# emonGLCD_V1_4.net
KiCad netlist of a schematic drawn in EAGLE
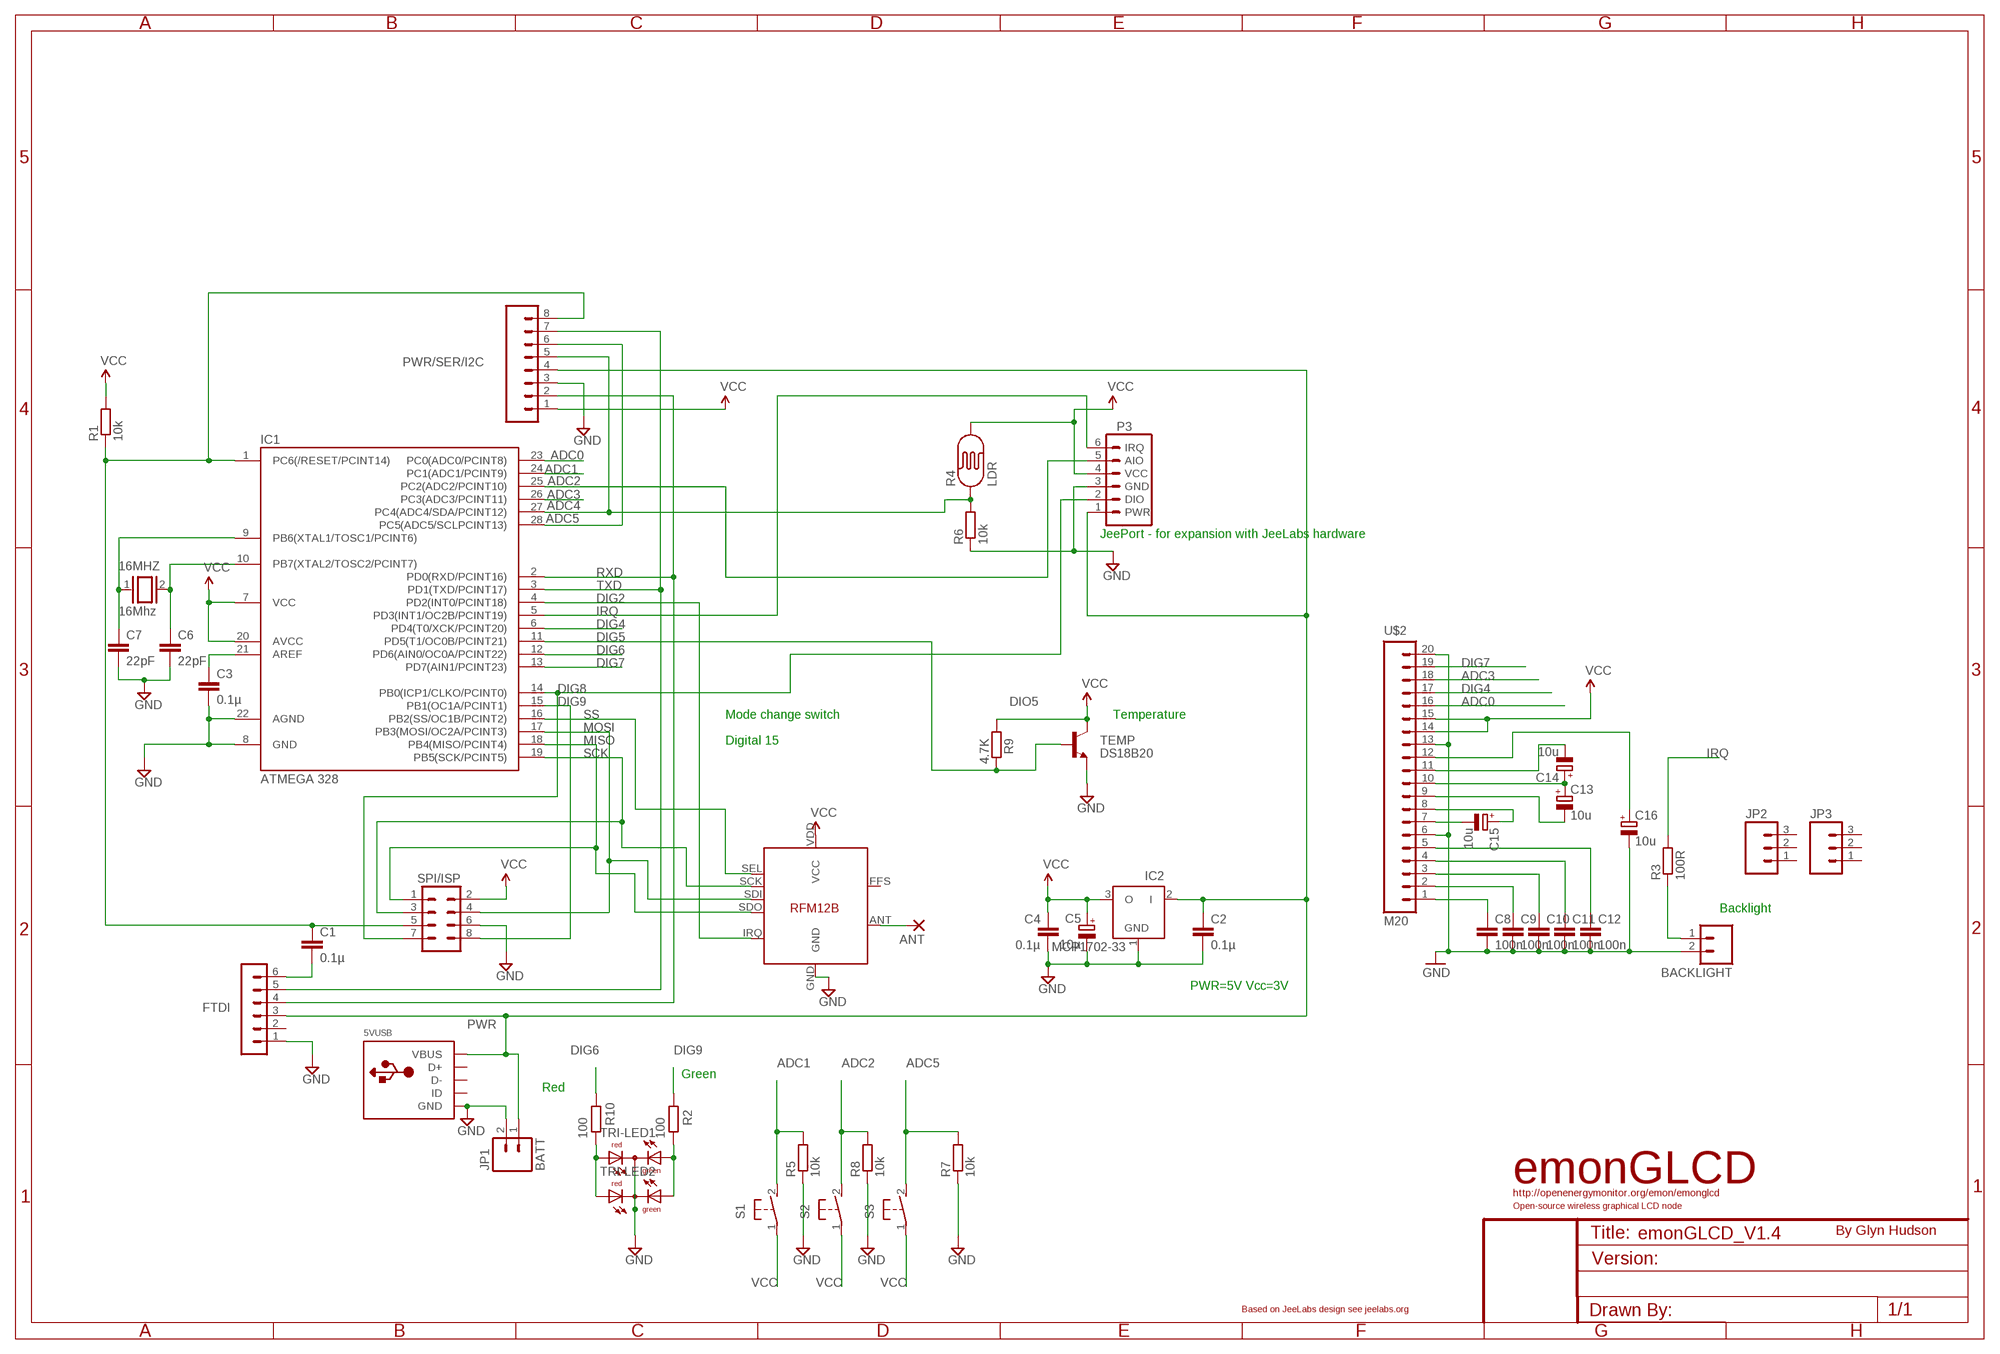
[diagram p0: schematic, sheet 1]

(export (version "E")
  (design (tool "Eeschema 10.0.6"))
  (components
    (comp (ref "5VUSB")
      (value "USBMOLEX")
      (footprint "eagle-import:USB-MINIB-THM-MOLEX")
      (libsource (lib "eagle-import") (part "USBMOLEX"))
    )
    (comp (ref "16MHZ")
      (value "16Mhz")
      (footprint "eagle-import:QS")
      (libsource (lib "eagle-import") (part "XTAL/S"))
    )
    (comp (ref "ANT")
      (value "1,6/0,8")
      (footprint "eagle-import:1,6_0,8")
      (libsource (lib "eagle-import") (part "1,6/0,8"))
    )
    (comp (ref "BACKLIGHT")
      (value "M02PTH")
      (footprint "eagle-import:1X02")
      (libsource (lib "eagle-import") (part "M02PTH"))
    )
    (comp (ref "C1")
      (value "0.1µ")
      (footprint "eagle-import:C025-024X044")
      (libsource (lib "eagle-import") (part "C-EU025-024X044"))
    )
    (comp (ref "C2")
      (value "0.1µ")
      (footprint "eagle-import:C025-024X044")
      (libsource (lib "eagle-import") (part "C-EU025-024X044"))
    )
    (comp (ref "C3")
      (value "0.1µ")
      (footprint "eagle-import:C025-024X044")
      (libsource (lib "eagle-import") (part "C-EU025-024X044"))
    )
    (comp (ref "C4")
      (value "0.1µ")
      (footprint "eagle-import:C025-024X044")
      (libsource (lib "eagle-import") (part "C-EU025-024X044"))
    )
    (comp (ref "C5")
      (value "10µ")
      (footprint "eagle-import:E1,8-4")
      (libsource (lib "eagle-import") (part "CPOL-EUE1.8-4"))
    )
    (comp (ref "C6")
      (value "22pF")
      (footprint "eagle-import:C2.5-2")
      (libsource (lib "eagle-import") (part "C2.5/2"))
    )
    (comp (ref "C7")
      (value "22pF")
      (footprint "eagle-import:C2.5-2")
      (libsource (lib "eagle-import") (part "C2.5/2"))
    )
    (comp (ref "C8")
      (value "100n")
      (footprint "eagle-import:C2.5-2")
      (libsource (lib "eagle-import") (part "C2.5/2"))
    )
    (comp (ref "C9")
      (value "100n")
      (footprint "eagle-import:C2.5-2")
      (libsource (lib "eagle-import") (part "C2.5/2"))
    )
    (comp (ref "C10")
      (value "100n")
      (footprint "eagle-import:C2.5-2")
      (libsource (lib "eagle-import") (part "C2.5/2"))
    )
    (comp (ref "C11")
      (value "100n")
      (footprint "eagle-import:C2.5-2")
      (libsource (lib "eagle-import") (part "C2.5/2"))
    )
    (comp (ref "C12")
      (value "100n")
      (footprint "eagle-import:C2.5-2")
      (libsource (lib "eagle-import") (part "C2.5/2"))
    )
    (comp (ref "C13")
      (value "10u")
      (footprint "eagle-import:E1,8-4")
      (libsource (lib "eagle-import") (part "CPOL-EUE1.8-4"))
    )
    (comp (ref "C14")
      (value "10u")
      (footprint "eagle-import:E1,8-4")
      (libsource (lib "eagle-import") (part "CPOL-EUE1.8-4"))
    )
    (comp (ref "C15")
      (value "10u")
      (footprint "eagle-import:E1,8-4")
      (libsource (lib "eagle-import") (part "CPOL-EUE1.8-4"))
    )
    (comp (ref "C16")
      (value "10u")
      (footprint "eagle-import:E1,8-4")
      (libsource (lib "eagle-import") (part "CPOL-EUE1.8-4"))
    )
    (comp (ref "FTDI")
      (value "FTDI")
      (footprint "eagle-import:MA06-1")
      (libsource (lib "eagle-import") (part "MA06-1"))
    )
    (comp (ref "IC1")
      (value "ATMEGA 328")
      (footprint "eagle-import:DIL28-3")
      (libsource (lib "eagle-import") (part "ATMEGA48/88/168-PU"))
    )
    (comp (ref "IC2")
      (value "MCP1702-33")
      (footprint "eagle-import:TO92")
      (libsource (lib "eagle-import") (part "MCP1702Z"))
    )
    (comp (ref "JP1")
      (value "BATT")
      (footprint "eagle-import:1X02_LOCK_LONGPADS")
      (libsource (lib "eagle-import") (part "M02LOCK_LONGPADS"))
    )
    (comp (ref "JP2")
      (value "M03PTH")
      (footprint "eagle-import:1X03")
      (libsource (lib "eagle-import") (part "M03PTH"))
    )
    (comp (ref "JP3")
      (value "M03PTH")
      (footprint "eagle-import:1X03")
      (libsource (lib "eagle-import") (part "M03PTH"))
    )
    (comp (ref "P3")
      (value "JEEPORT")
      (footprint "eagle-import:PORT6PIN")
      (libsource (lib "eagle-import") (part "JEEPORT-LONGPADS"))
    )
    (comp (ref "PWR/SER/I2C")
      (value "M08")
      (footprint "eagle-import:1X08")
      (libsource (lib "eagle-import") (part "M08"))
    )
    (comp (ref "R1")
      (value "10k")
      (footprint "eagle-import:0204_7")
      (libsource (lib "eagle-import") (part "resistor_R-EU_0204/7"))
    )
    (comp (ref "R2")
      (value "100")
      (footprint "eagle-import:0204_7")
      (libsource (lib "eagle-import") (part "R-EU_0204/7"))
    )
    (comp (ref "R3")
      (value "100R")
      (footprint "eagle-import:0204_7")
      (libsource (lib "eagle-import") (part "R-EU_0204/7"))
    )
    (comp (ref "R4")
      (value "LDR")
      (footprint "eagle-import:PHOTOCELL")
      (libsource (lib "eagle-import") (part "PHOTOCELLPTH"))
    )
    (comp (ref "R5")
      (value "10k")
      (footprint "eagle-import:0204_7")
      (libsource (lib "eagle-import") (part "resistor_R-EU_0204/7"))
    )
    (comp (ref "R6")
      (value "10k")
      (footprint "eagle-import:0204_7")
      (libsource (lib "eagle-import") (part "resistor_R-EU_0204/7"))
    )
    (comp (ref "R7")
      (value "10k")
      (footprint "eagle-import:0204_7")
      (libsource (lib "eagle-import") (part "resistor_R-EU_0204/7"))
    )
    (comp (ref "R8")
      (value "10k")
      (footprint "eagle-import:0204_7")
      (libsource (lib "eagle-import") (part "resistor_R-EU_0204/7"))
    )
    (comp (ref "R9")
      (value "4.7K")
      (footprint "eagle-import:0204_7")
      (libsource (lib "eagle-import") (part "R-EU_0204/7"))
    )
    (comp (ref "R10")
      (value "100")
      (footprint "eagle-import:0204_7")
      (libsource (lib "eagle-import") (part "R-EU_0204/7"))
    )
    (comp (ref "S1")
      (value "31-XX")
      (footprint "eagle-import:B3F-31XX")
      (libsource (lib "eagle-import") (part "31-XX"))
    )
    (comp (ref "S2")
      (value "31-XX")
      (footprint "eagle-import:B3F-31XX")
      (libsource (lib "eagle-import") (part "31-XX"))
    )
    (comp (ref "S3")
      (value "31-XX")
      (footprint "eagle-import:B3F-31XX")
      (libsource (lib "eagle-import") (part "31-XX"))
    )
    (comp (ref "SV7")
      (value "SPI/ISP")
      (footprint "eagle-import:MA04-2")
      (libsource (lib "eagle-import") (part "MA04-2"))
    )
    (comp (ref "TEMP")
      (value "DS18B20")
      (footprint "eagle-import:TO-92")
      (libsource (lib "eagle-import") (part "TRANSISTOR_NPNTO92"))
    )
    (comp (ref "TRI-LED1")
      (value "DUOLED5MM")
      (footprint "eagle-import:DUOLED5MM")
      (libsource (lib "eagle-import") (part "DUOLED5MM"))
    )
    (comp (ref "TRI-LED2")
      (value "DUOLED5MM")
      (footprint "eagle-import:DUOLED5MM")
      (libsource (lib "eagle-import") (part "DUOLED5MM"))
    )
    (comp (ref "U$1")
      (value "RFM12B")
      (footprint "eagle-import:RFM12B")
      (libsource (lib "eagle-import") (part "RFM12B"))
    )
    (comp (ref "U$2")
      (value "M20")
      (footprint "eagle-import:1X20")
      (libsource (lib "eagle-import") (part "M20"))
    )
  )
  (nets
    (net (code "1") (name "/ADC0") (class "Default")
      (node (ref "IC1") (pin "23") (pinfunction "PC0(ADC0/PCINT8)_23") (pintype "bidirectional"))
      (node (ref "U$2") (pin "16") (pinfunction "16_16") (pintype "passive"))
    )
    (net (code "2") (name "/ADC1") (class "Default")
      (node (ref "IC1") (pin "24") (pinfunction "PC1(ADC1/PCINT9)_24") (pintype "bidirectional"))
      (node (ref "R5") (pin "2") (pinfunction "2_2") (pintype "passive"))
      (node (ref "S1") (pin "2") (pinfunction "S_2") (pintype "passive"))
    )
    (net (code "3") (name "/ADC2") (class "Default")
      (node (ref "IC1") (pin "25") (pinfunction "PC2(ADC2/PCINT10)_25") (pintype "bidirectional"))
      (node (ref "P3") (pin "5") (pinfunction "AIO_5") (pintype "bidirectional"))
      (node (ref "R8") (pin "2") (pinfunction "2_2") (pintype "passive"))
      (node (ref "S2") (pin "2") (pinfunction "S_2") (pintype "passive"))
    )
    (net (code "4") (name "/ADC3") (class "Default")
      (node (ref "IC1") (pin "26") (pinfunction "PC3(ADC3/PCINT11)_26") (pintype "bidirectional"))
      (node (ref "U$2") (pin "18") (pinfunction "18_18") (pintype "passive"))
    )
    (net (code "5") (name "/ADC4") (class "Default")
      (node (ref "IC1") (pin "27") (pinfunction "PC4(ADC4/SDA/PCINT12)_27") (pintype "bidirectional"))
      (node (ref "PWR/SER/I2C") (pin "5") (pinfunction "5_5") (pintype "passive"))
      (node (ref "R4") (pin "1") (pinfunction "P$1_1") (pintype "bidirectional"))
      (node (ref "R6") (pin "2") (pinfunction "2_2") (pintype "passive"))
    )
    (net (code "6") (name "/ADC5") (class "Default")
      (node (ref "IC1") (pin "28") (pinfunction "PC5(ADC5/SCLPCINT13)_28") (pintype "bidirectional"))
      (node (ref "PWR/SER/I2C") (pin "6") (pinfunction "6_6") (pintype "passive"))
      (node (ref "R7") (pin "2") (pinfunction "2_2") (pintype "passive"))
      (node (ref "S3") (pin "2") (pinfunction "S_2") (pintype "passive"))
    )
    (net (code "7") (name "/DIG2") (class "Default")
      (node (ref "IC1") (pin "4") (pinfunction "PD2(INT0/PCINT18)_4") (pintype "bidirectional"))
      (node (ref "U$1") (pin "IRQ") (pinfunction "IRQ_IRQ") (pintype "open_collector"))
    )
    (net (code "8") (name "/DIG4") (class "Default")
      (node (ref "IC1") (pin "6") (pinfunction "PD4(T0/XCK/PCINT20)_6") (pintype "bidirectional"))
      (node (ref "U$2") (pin "17") (pinfunction "17_17") (pintype "passive"))
    )
    (net (code "9") (name "/DIG5") (class "Default")
      (node (ref "IC1") (pin "11") (pinfunction "PD5(T1/OC0B/PCINT21)_11") (pintype "bidirectional"))
      (node (ref "R9") (pin "2") (pinfunction "2_2") (pintype "passive"))
      (node (ref "TEMP") (pin "2") (pinfunction "B_2") (pintype "passive"))
    )
    (net (code "10") (name "/DIG6") (class "Default")
      (node (ref "IC1") (pin "12") (pinfunction "PD6(AIN0/OC0A/PCINT22)_12") (pintype "bidirectional"))
      (node (ref "R10") (pin "2") (pinfunction "2_2") (pintype "passive"))
    )
    (net (code "11") (name "/DIG7") (class "Default")
      (node (ref "IC1") (pin "13") (pinfunction "PD7(AIN1/PCINT23)_13") (pintype "bidirectional"))
      (node (ref "U$2") (pin "19") (pinfunction "19_19") (pintype "passive"))
    )
    (net (code "12") (name "/DIG8") (class "Default")
      (node (ref "IC1") (pin "14") (pinfunction "PB0(ICP1/CLKO/PCINT0)_14") (pintype "bidirectional"))
      (node (ref "P3") (pin "2") (pinfunction "DIO_2") (pintype "bidirectional"))
      (node (ref "SV7") (pin "7") (pinfunction "7_7") (pintype "passive"))
    )
    (net (code "13") (name "/DIG9") (class "Default")
      (node (ref "IC1") (pin "15") (pinfunction "PB1(OC1A/PCINT1)_15") (pintype "bidirectional"))
      (node (ref "R2") (pin "2") (pinfunction "2_2") (pintype "passive"))
      (node (ref "SV7") (pin "8") (pinfunction "8_8") (pintype "passive"))
    )
    (net (code "14") (name "/IRQ") (class "Default")
      (node (ref "IC1") (pin "5") (pinfunction "PD3(INT1/OC2B/PCINT19)_5") (pintype "bidirectional"))
      (node (ref "P3") (pin "6") (pinfunction "IRQ_6") (pintype "bidirectional"))
      (node (ref "R3") (pin "2") (pinfunction "2_2") (pintype "passive"))
    )
    (net (code "15") (name "/MISO") (class "Default")
      (node (ref "IC1") (pin "18") (pinfunction "PB4(MISO/PCINT4)_18") (pintype "bidirectional"))
      (node (ref "SV7") (pin "1") (pinfunction "1_1") (pintype "passive"))
      (node (ref "U$1") (pin "SDO") (pinfunction "SDO_SDO") (pintype "output"))
    )
    (net (code "16") (name "/MOSI") (class "Default")
      (node (ref "IC1") (pin "17") (pinfunction "PB3(MOSI/OC2A/PCINT3)_17") (pintype "bidirectional"))
      (node (ref "SV7") (pin "4") (pinfunction "4_4") (pintype "passive"))
      (node (ref "U$1") (pin "SDI") (pinfunction "SDI_SDI") (pintype "input"))
    )
    (net (code "17") (name "/PWR") (class "Default")
      (node (ref "5VUSB") (pin "VBUS") (pinfunction "VBUS_VBUS") (pintype "power_in"))
      (node (ref "C2") (pin "1") (pinfunction "1_1") (pintype "passive"))
      (node (ref "FTDI") (pin "3") (pinfunction "3_3") (pintype "passive"))
      (node (ref "IC2") (pin "2") (pinfunction "I_2") (pintype "input"))
      (node (ref "JP1") (pin "1") (pinfunction "1_1") (pintype "passive"))
      (node (ref "P3") (pin "1") (pinfunction "PWR_1") (pintype "power_in"))
      (node (ref "PWR/SER/I2C") (pin "4") (pinfunction "4_4") (pintype "passive"))
    )
    (net (code "18") (name "/RXD") (class "Default")
      (node (ref "FTDI") (pin "4") (pinfunction "4_4") (pintype "passive"))
      (node (ref "IC1") (pin "2") (pinfunction "PD0(RXD/PCINT16)_2") (pintype "bidirectional"))
      (node (ref "PWR/SER/I2C") (pin "2") (pinfunction "2_2") (pintype "passive"))
    )
    (net (code "19") (name "/SCK") (class "Default")
      (node (ref "IC1") (pin "19") (pinfunction "PB5(SCK/PCINT5)_19") (pintype "bidirectional"))
      (node (ref "SV7") (pin "3") (pinfunction "3_3") (pintype "passive"))
      (node (ref "U$1") (pin "SCK") (pinfunction "SCK_SCK") (pintype "input"))
    )
    (net (code "20") (name "/SS") (class "Default")
      (node (ref "IC1") (pin "16") (pinfunction "PB2(SS/OC1B/PCINT2)_16") (pintype "bidirectional"))
      (node (ref "U$1") (pin "SEL") (pinfunction "SEL_SEL") (pintype "input"))
    )
    (net (code "21") (name "/TXD") (class "Default")
      (node (ref "FTDI") (pin "5") (pinfunction "5_5") (pintype "passive"))
      (node (ref "IC1") (pin "3") (pinfunction "PD1(TXD/PCINT17)_3") (pintype "bidirectional"))
      (node (ref "PWR/SER/I2C") (pin "7") (pinfunction "7_7") (pintype "passive"))
    )
    (net (code "22") (name "GND") (class "Default")
      (node (ref "5VUSB") (pin "GND") (pinfunction "GND_GND") (pintype "power_in"))
      (node (ref "BACKLIGHT") (pin "2") (pinfunction "2_2") (pintype "passive"))
      (node (ref "C10") (pin "2") (pinfunction "2_2") (pintype "passive"))
      (node (ref "C11") (pin "2") (pinfunction "2_2") (pintype "passive"))
      (node (ref "C12") (pin "2") (pinfunction "2_2") (pintype "passive"))
      (node (ref "C16") (pin "-") (pinfunction "-_-") (pintype "passive"))
      (node (ref "C2") (pin "2") (pinfunction "2_2") (pintype "passive"))
      (node (ref "C3") (pin "2") (pinfunction "2_2") (pintype "passive"))
      (node (ref "C4") (pin "2") (pinfunction "2_2") (pintype "passive"))
      (node (ref "C5") (pin "-") (pinfunction "-_-") (pintype "passive"))
      (node (ref "C6") (pin "2") (pinfunction "2_2") (pintype "passive"))
      (node (ref "C7") (pin "2") (pinfunction "2_2") (pintype "passive"))
      (node (ref "C8") (pin "2") (pinfunction "2_2") (pintype "passive"))
      (node (ref "C9") (pin "2") (pinfunction "2_2") (pintype "passive"))
      (node (ref "FTDI") (pin "1") (pinfunction "1_1") (pintype "passive"))
      (node (ref "IC1") (pin "22") (pinfunction "AGND_22") (pintype "power_in"))
      (node (ref "IC1") (pin "8") (pinfunction "GND_8") (pintype "power_in"))
      (node (ref "IC2") (pin "1") (pinfunction "GND_1") (pintype "power_in"))
      (node (ref "JP1") (pin "2") (pinfunction "2_2") (pintype "passive"))
      (node (ref "P3") (pin "3") (pinfunction "GND_3") (pintype "power_in"))
      (node (ref "PWR/SER/I2C") (pin "3") (pinfunction "3_3") (pintype "passive"))
      (node (ref "R5") (pin "1") (pinfunction "1_1") (pintype "passive"))
      (node (ref "R6") (pin "1") (pinfunction "1_1") (pintype "passive"))
      (node (ref "R7") (pin "1") (pinfunction "1_1") (pintype "passive"))
      (node (ref "R8") (pin "1") (pinfunction "1_1") (pintype "passive"))
      (node (ref "SV7") (pin "6") (pinfunction "6_6") (pintype "passive"))
      (node (ref "TEMP") (pin "1") (pinfunction "E_1") (pintype "passive"))
      (node (ref "TRI-LED1") (pin "K") (pinfunction "C_K") (pintype "passive"))
      (node (ref "TRI-LED2") (pin "K") (pinfunction "C_K") (pintype "passive"))
      (node (ref "U$1") (pin "GND") (pinfunction "GND_GND") (pintype "power_in"))
      (node (ref "U$2") (pin "13") (pinfunction "13_13") (pintype "passive"))
      (node (ref "U$2") (pin "20") (pinfunction "20_20") (pintype "passive"))
      (node (ref "U$2") (pin "6") (pinfunction "6_6") (pintype "passive"))
    )
    (net (code "23") (name "Net-(ANT-P)") (class "Default")
      (node (ref "ANT") (pin "1") (pinfunction "P_1") (pintype "passive"))
      (node (ref "U$1") (pin "ANT") (pinfunction "ANT_ANT") (pintype "passive"))
    )
    (net (code "24") (name "Net-(BACKLIGHT-Pad1)") (class "Default")
      (node (ref "BACKLIGHT") (pin "1") (pinfunction "1_1") (pintype "passive"))
      (node (ref "R3") (pin "1") (pinfunction "1_1") (pintype "passive"))
    )
    (net (code "25") (name "Net-(C1-Pad2)") (class "Default")
      (node (ref "C1") (pin "2") (pinfunction "2_2") (pintype "passive"))
      (node (ref "FTDI") (pin "6") (pinfunction "6_6") (pintype "passive"))
    )
    (net (code "26") (name "Net-(C8-Pad1)") (class "Default")
      (node (ref "C8") (pin "1") (pinfunction "1_1") (pintype "passive"))
      (node (ref "U$2") (pin "1") (pinfunction "1_1") (pintype "passive"))
    )
    (net (code "27") (name "Net-(C9-Pad1)") (class "Default")
      (node (ref "C9") (pin "1") (pinfunction "1_1") (pintype "passive"))
      (node (ref "U$2") (pin "2") (pinfunction "2_2") (pintype "passive"))
    )
    (net (code "28") (name "Net-(C10-Pad1)") (class "Default")
      (node (ref "C10") (pin "1") (pinfunction "1_1") (pintype "passive"))
      (node (ref "U$2") (pin "3") (pinfunction "3_3") (pintype "passive"))
    )
    (net (code "29") (name "Net-(C11-Pad1)") (class "Default")
      (node (ref "C11") (pin "1") (pinfunction "1_1") (pintype "passive"))
      (node (ref "U$2") (pin "4") (pinfunction "4_4") (pintype "passive"))
    )
    (net (code "30") (name "Net-(C12-Pad1)") (class "Default")
      (node (ref "C12") (pin "1") (pinfunction "1_1") (pintype "passive"))
      (node (ref "U$2") (pin "5") (pinfunction "5_5") (pintype "passive"))
    )
    (net (code "31") (name "Net-(C13-Pad+)") (class "Default")
      (node (ref "C13") (pin "+") (pinfunction "+_+") (pintype "passive"))
      (node (ref "C14") (pin "+") (pinfunction "+_+") (pintype "passive"))
      (node (ref "U$2") (pin "10") (pinfunction "10_10") (pintype "passive"))
    )
    (net (code "32") (name "Net-(C13-Pad-)") (class "Default")
      (node (ref "C13") (pin "-") (pinfunction "-_-") (pintype "passive"))
      (node (ref "U$2") (pin "9") (pinfunction "9_9") (pintype "passive"))
    )
    (net (code "33") (name "Net-(C14-Pad-)") (class "Default")
      (node (ref "C14") (pin "-") (pinfunction "-_-") (pintype "passive"))
      (node (ref "U$2") (pin "11") (pinfunction "11_11") (pintype "passive"))
    )
    (net (code "34") (name "Net-(C15-Pad+)") (class "Default")
      (node (ref "C15") (pin "+") (pinfunction "+_+") (pintype "passive"))
      (node (ref "U$2") (pin "8") (pinfunction "8_8") (pintype "passive"))
    )
    (net (code "35") (name "Net-(C15-Pad-)") (class "Default")
      (node (ref "C15") (pin "-") (pinfunction "-_-") (pintype "passive"))
      (node (ref "U$2") (pin "7") (pinfunction "7_7") (pintype "passive"))
    )
    (net (code "36") (name "Net-(C16-Pad+)") (class "Default")
      (node (ref "C16") (pin "+") (pinfunction "+_+") (pintype "passive"))
      (node (ref "U$2") (pin "12") (pinfunction "12_12") (pintype "passive"))
    )
    (net (code "37") (name "Net-(IC1-AREF)") (class "Default")
      (node (ref "C3") (pin "1") (pinfunction "1_1") (pintype "passive"))
      (node (ref "IC1") (pin "21") (pinfunction "AREF_21") (pintype "passive"))
    )
    (net (code "38") (name "Net-(IC1-PB6(XTAL1{slash}TOSC1{slash}PCINT6))") (class "Default")
      (node (ref "16MHZ") (pin "1") (pinfunction "1_1") (pintype "passive"))
      (node (ref "C7") (pin "1") (pinfunction "1_1") (pintype "passive"))
      (node (ref "IC1") (pin "9") (pinfunction "PB6(XTAL1/TOSC1/PCINT6)_9") (pintype "bidirectional"))
    )
    (net (code "39") (name "Net-(IC1-PB7(XTAL2{slash}TOSC2{slash}PCINT7))") (class "Default")
      (node (ref "16MHZ") (pin "2") (pinfunction "2_2") (pintype "passive"))
      (node (ref "C6") (pin "1") (pinfunction "1_1") (pintype "passive"))
      (node (ref "IC1") (pin "10") (pinfunction "PB7(XTAL2/TOSC2/PCINT7)_10") (pintype "bidirectional"))
    )
    (net (code "40") (name "Net-(IC1-PC6({slash}RESET{slash}PCINT14))") (class "Default")
      (node (ref "C1") (pin "1") (pinfunction "1_1") (pintype "passive"))
      (node (ref "IC1") (pin "1") (pinfunction "PC6(/RESET/PCINT14)_1") (pintype "bidirectional"))
      (node (ref "PWR/SER/I2C") (pin "8") (pinfunction "8_8") (pintype "passive"))
      (node (ref "R1") (pin "1") (pinfunction "1_1") (pintype "passive"))
      (node (ref "SV7") (pin "5") (pinfunction "5_5") (pintype "passive"))
    )
    (net (code "41") (name "Net-(R2-Pad1)") (class "Default")
      (node (ref "R2") (pin "1") (pinfunction "1_1") (pintype "passive"))
      (node (ref "TRI-LED1") (pin "AG") (pinfunction "AG_AG") (pintype "passive"))
      (node (ref "TRI-LED2") (pin "AG") (pinfunction "AG_AG") (pintype "passive"))
    )
    (net (code "42") (name "Net-(R10-Pad1)") (class "Default")
      (node (ref "R10") (pin "1") (pinfunction "1_1") (pintype "passive"))
      (node (ref "TRI-LED1") (pin "AR") (pinfunction "AR_AR") (pintype "passive"))
      (node (ref "TRI-LED2") (pin "AR") (pinfunction "AR_AR") (pintype "passive"))
    )
    (net (code "43") (name "VCC") (class "Default")
      (node (ref "C4") (pin "1") (pinfunction "1_1") (pintype "passive"))
      (node (ref "C5") (pin "+") (pinfunction "+_+") (pintype "passive"))
      (node (ref "IC1") (pin "20") (pinfunction "AVCC_20") (pintype "passive"))
      (node (ref "IC1") (pin "7") (pinfunction "VCC_7") (pintype "power_in"))
      (node (ref "IC2") (pin "3") (pinfunction "O_3") (pintype "input"))
      (node (ref "P3") (pin "4") (pinfunction "VCC_4") (pintype "power_in"))
      (node (ref "PWR/SER/I2C") (pin "1") (pinfunction "1_1") (pintype "passive"))
      (node (ref "R1") (pin "2") (pinfunction "2_2") (pintype "passive"))
      (node (ref "R4") (pin "2") (pinfunction "P$2_2") (pintype "bidirectional"))
      (node (ref "R9") (pin "1") (pinfunction "1_1") (pintype "passive"))
      (node (ref "S1") (pin "1") (pinfunction "P_1") (pintype "passive"))
      (node (ref "S2") (pin "1") (pinfunction "P_1") (pintype "passive"))
      (node (ref "S3") (pin "1") (pinfunction "P_1") (pintype "passive"))
      (node (ref "SV7") (pin "2") (pinfunction "2_2") (pintype "passive"))
      (node (ref "TEMP") (pin "3") (pinfunction "C_3") (pintype "passive"))
      (node (ref "U$1") (pin "VDD") (pinfunction "VCC_VDD") (pintype "power_in"))
      (node (ref "U$2") (pin "14") (pinfunction "14_14") (pintype "passive"))
      (node (ref "U$2") (pin "15") (pinfunction "15_15") (pintype "passive"))
    )
    (net (code "44") (name "unconnected-(5VUSB-PadD+)") (class "Default")
      (node (ref "5VUSB") (pin "D+") (pinfunction "D+_D+") (pintype "bidirectional"))
    )
    (net (code "45") (name "unconnected-(5VUSB-PadD-)") (class "Default")
      (node (ref "5VUSB") (pin "D-") (pinfunction "D-_D-") (pintype "bidirectional"))
    )
    (net (code "46") (name "unconnected-(5VUSB-PadID)") (class "Default")
      (node (ref "5VUSB") (pin "ID") (pinfunction "ID_ID") (pintype "bidirectional"))
    )
    (net (code "47") (name "unconnected-(FTDI-Pad2)") (class "Default")
      (node (ref "FTDI") (pin "2") (pinfunction "2_2") (pintype "passive"))
    )
    (net (code "48") (name "unconnected-(JP2-Pad1)") (class "Default")
      (node (ref "JP2") (pin "1") (pinfunction "1_1") (pintype "passive"))
    )
    (net (code "49") (name "unconnected-(JP2-Pad2)") (class "Default")
      (node (ref "JP2") (pin "2") (pinfunction "2_2") (pintype "passive"))
    )
    (net (code "50") (name "unconnected-(JP2-Pad3)") (class "Default")
      (node (ref "JP2") (pin "3") (pinfunction "3_3") (pintype "passive"))
    )
    (net (code "51") (name "unconnected-(JP3-Pad1)") (class "Default")
      (node (ref "JP3") (pin "1") (pinfunction "1_1") (pintype "passive"))
    )
    (net (code "52") (name "unconnected-(JP3-Pad2)") (class "Default")
      (node (ref "JP3") (pin "2") (pinfunction "2_2") (pintype "passive"))
    )
    (net (code "53") (name "unconnected-(JP3-Pad3)") (class "Default")
      (node (ref "JP3") (pin "3") (pinfunction "3_3") (pintype "passive"))
    )
    (net (code "54") (name "unconnected-(U$1-PadFFS)") (class "Default")
      (node (ref "U$1") (pin "FFS") (pinfunction "FFS_FFS") (pintype "bidirectional"))
    )
  )
)
